# SCHEMATIC.net
KiCad netlist of a schematic drawn in EAGLE
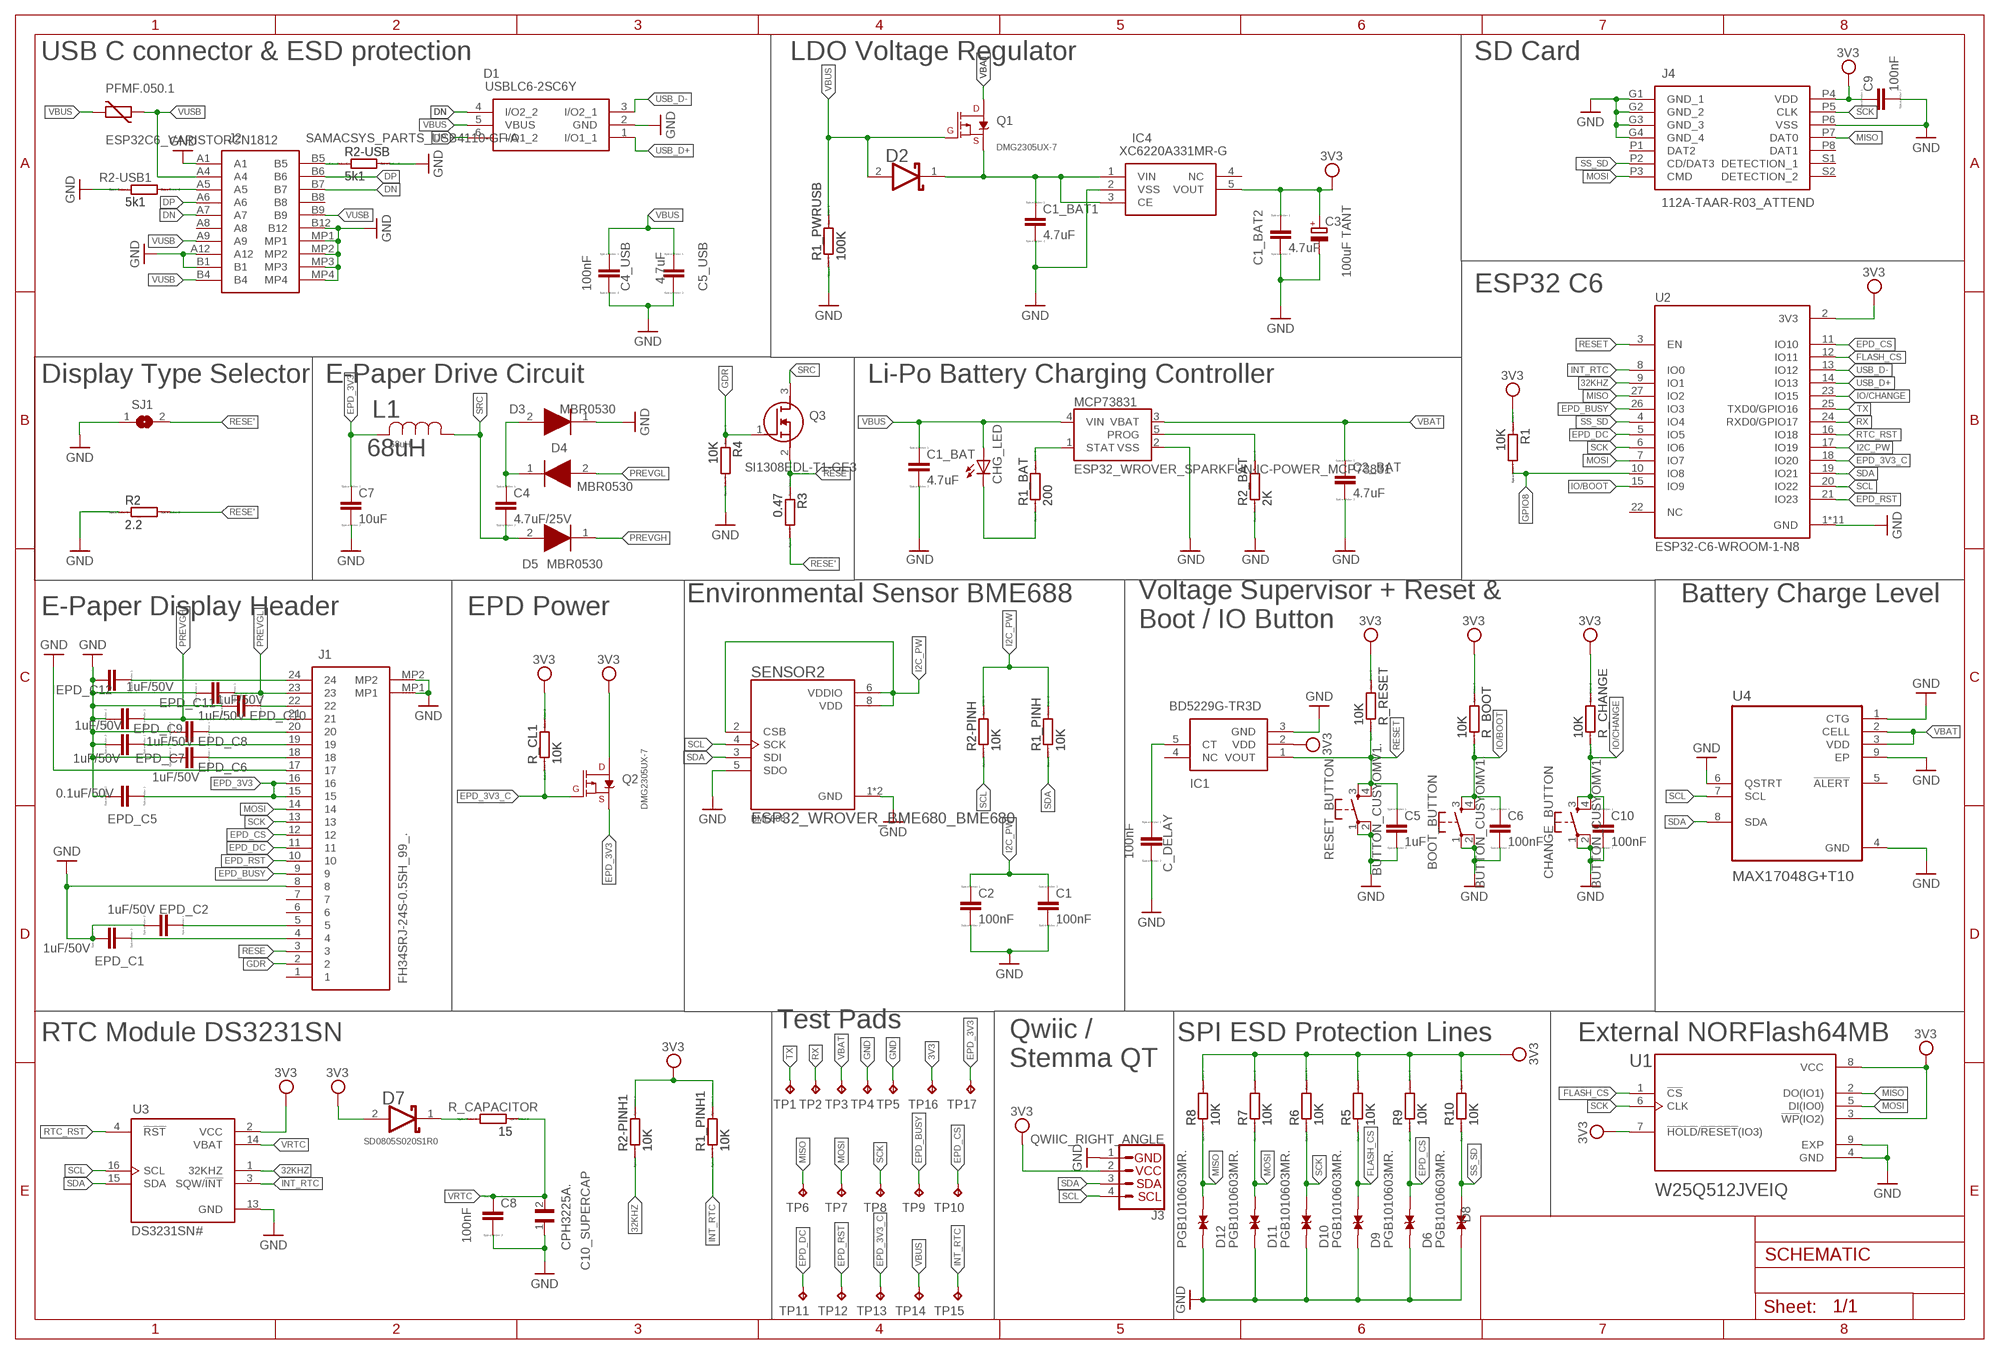
[diagram p0: schematic, sheet 1]

(export (version "E")
  (design (tool "Eeschema 10.0.6"))
  (components
    (comp (ref "BOOT_BUTTON")
      (value "BUTTON_CUSYOMV1.")
      (footprint "eagle-import:MYBUTTON")
      (libsource (lib "eagle-import") (part "BUTTON_CUSYOMV1."))
    )
    (comp (ref "C1")
      (value "100nF")
      (footprint "eagle-import:EAGLE-LTSPICE_C0402")
      (libsource (lib "eagle-import") (part "ESP32_WROVER_EAGLE-LTSPICE_CC0402"))
    )
    (comp (ref "C1_BAT")
      (value "4.7uF")
      (footprint "eagle-import:EAGLE-LTSPICE_C0402")
      (libsource (lib "eagle-import") (part "ESP32_WROVER_EAGLE-LTSPICE_CC0402"))
    )
    (comp (ref "C1_BAT1")
      (value "4.7uF")
      (footprint "eagle-import:EAGLE-LTSPICE_C0402")
      (libsource (lib "eagle-import") (part "ESP32_WROVER_EAGLE-LTSPICE_CC0402"))
    )
    (comp (ref "C1_BAT2")
      (value "4.7uF")
      (footprint "eagle-import:EAGLE-LTSPICE_C0402")
      (libsource (lib "eagle-import") (part "ESP32_WROVER_EAGLE-LTSPICE_CC0402"))
    )
    (comp (ref "C2")
      (value "100nF")
      (footprint "eagle-import:EAGLE-LTSPICE_C0402")
      (libsource (lib "eagle-import") (part "ESP32_WROVER_EAGLE-LTSPICE_CC0402"))
    )
    (comp (ref "C2_BAT")
      (value "4.7uF")
      (footprint "eagle-import:EAGLE-LTSPICE_C0402")
      (libsource (lib "eagle-import") (part "ESP32_WROVER_EAGLE-LTSPICE_CC0402"))
    )
    (comp (ref "C3")
      (value "100uF TANT")
      (footprint "eagle-import:RCL_CT3528")
      (libsource (lib "eagle-import") (part "RCL_CPOL-EUCT3528"))
    )
    (comp (ref "C4")
      (value "4.7uF/25V")
      (footprint "eagle-import:EAGLE-LTSPICE_C0402")
      (libsource (lib "eagle-import") (part "ESP32_WROVER_EAGLE-LTSPICE_CC0402"))
    )
    (comp (ref "C4_USB")
      (value "100nF")
      (footprint "eagle-import:EAGLE-LTSPICE_C0402")
      (libsource (lib "eagle-import") (part "ESP32_WROVER_EAGLE-LTSPICE_CC0402"))
    )
    (comp (ref "C5")
      (value "1uF")
      (footprint "eagle-import:EAGLE-LTSPICE_C0402")
      (libsource (lib "eagle-import") (part "ESP32_WROVER_EAGLE-LTSPICE_CC0402"))
    )
    (comp (ref "C5_USB")
      (value "4.7uF")
      (footprint "eagle-import:EAGLE-LTSPICE_C0402")
      (libsource (lib "eagle-import") (part "ESP32_WROVER_EAGLE-LTSPICE_CC0402"))
    )
    (comp (ref "C6")
      (value "100nF")
      (footprint "eagle-import:EAGLE-LTSPICE_C0402")
      (libsource (lib "eagle-import") (part "ESP32_WROVER_EAGLE-LTSPICE_CC0402"))
    )
    (comp (ref "C7")
      (value "10uF")
      (footprint "eagle-import:EAGLE-LTSPICE_C0402")
      (libsource (lib "eagle-import") (part "ESP32_WROVER_EAGLE-LTSPICE_CC0402"))
    )
    (comp (ref "C8")
      (value "100nF")
      (footprint "eagle-import:EAGLE-LTSPICE_C0402")
      (libsource (lib "eagle-import") (part "ESP32_WROVER_EAGLE-LTSPICE_CC0402"))
    )
    (comp (ref "C9")
      (value "100nF")
      (footprint "eagle-import:EAGLE-LTSPICE_C0402")
      (libsource (lib "eagle-import") (part "EAGLE-LTSPICE_CC0402"))
    )
    (comp (ref "C10")
      (value "100nF")
      (footprint "eagle-import:EAGLE-LTSPICE_C0402")
      (libsource (lib "eagle-import") (part "ESP32_WROVER_EAGLE-LTSPICE_CC0402"))
    )
    (comp (ref "C10_SUPERCAP")
      (value "CPH3225A.")
      (footprint "eagle-import:CAPCP3225X100N")
      (libsource (lib "eagle-import") (part "CPH3225A."))
    )
    (comp (ref "CHANGE_BUTTON")
      (value "BUTTON_CUSYOMV1.")
      (footprint "eagle-import:MYBUTTON")
      (libsource (lib "eagle-import") (part "BUTTON_CUSYOMV1."))
    )
    (comp (ref "CHG_LED")
      (value "ADAFRUIT_LEDCHIP-LED0603")
      (footprint "eagle-import:ADAFRUIT_CHIP-LED0603")
      (libsource (lib "eagle-import") (part "ADAFRUIT_LEDCHIP-LED0603"))
    )
    (comp (ref "C_DELAY")
      (value "100nF")
      (footprint "eagle-import:EAGLE-LTSPICE_C0402")
      (libsource (lib "eagle-import") (part "ESP32_WROVER_EAGLE-LTSPICE_CC0402"))
    )
    (comp (ref "D1")
      (value "USBLC6-2SC6Y")
      (footprint "eagle-import:SOT95P280X145-6N")
      (fields (field (name "MF") "STMicroelectronics"))
      (libsource (lib "eagle-import") (part "USBLC6-2SC6Y"))
    )
    (comp (ref "D2")
      (value "ESP32_WROVER_AVX---SD0805S020S1R0_AVX_SD0805S020S1R0_0_0AVX_SD0805S020S1R0_0_0")
      (footprint "eagle-import:ESP32_WROVER_AVX---SD0805S020S1R0_AVX_SD0805S020S1R0_0")
      (libsource (lib "eagle-import") (part "ESP32_WROVER_AVX---SD0805S020S1R0_AVX_SD0805S020S1R0_0_0AVX_SD0805S020S1R0_0_0"))
    )
    (comp (ref "D3")
      (value "MBR0530")
      (footprint "eagle-import:SOD3716X135N")
      (fields (field (name "MF") "ON Semiconductor"))
      (libsource (lib "eagle-import") (part "MBR0530"))
    )
    (comp (ref "D4")
      (value "MBR0530")
      (footprint "eagle-import:SOD3716X135N")
      (fields (field (name "MF") "ON Semiconductor"))
      (libsource (lib "eagle-import") (part "MBR0530"))
    )
    (comp (ref "D5")
      (value "MBR0530")
      (footprint "eagle-import:SOD3716X135N")
      (fields (field (name "MF") "ON Semiconductor"))
      (libsource (lib "eagle-import") (part "MBR0530"))
    )
    (comp (ref "D6")
      (value "PGB1010603MR.")
      (footprint "eagle-import:DIOC1608X36N")
      (libsource (lib "eagle-import") (part "PGB1010603MR."))
    )
    (comp (ref "D7")
      (value "ESP32_WROVER_AVX---SD0805S020S1R0_AVX_SD0805S020S1R0_0_0AVX_SD0805S020S1R0_0_0")
      (footprint "eagle-import:ESP32_WROVER_AVX---SD0805S020S1R0_AVX_SD0805S020S1R0_0")
      (fields (field (name "D7") "SD0805S020S1R0"))
      (libsource (lib "eagle-import") (part "ESP32_WROVER_AVX---SD0805S020S1R0_AVX_SD0805S020S1R0_0_0AVX_SD0805S020S1R0_0_0"))
    )
    (comp (ref "D8")
      (value "PGB1010603MR.")
      (footprint "eagle-import:DIOC1608X36N")
      (libsource (lib "eagle-import") (part "PGB1010603MR."))
    )
    (comp (ref "D9")
      (value "PGB1010603MR.")
      (footprint "eagle-import:DIOC1608X36N")
      (libsource (lib "eagle-import") (part "PGB1010603MR."))
    )
    (comp (ref "D10")
      (value "PGB1010603MR.")
      (footprint "eagle-import:DIOC1608X36N")
      (libsource (lib "eagle-import") (part "PGB1010603MR."))
    )
    (comp (ref "D11")
      (value "PGB1010603MR.")
      (footprint "eagle-import:DIOC1608X36N")
      (libsource (lib "eagle-import") (part "PGB1010603MR."))
    )
    (comp (ref "D12")
      (value "PGB1010603MR.")
      (footprint "eagle-import:DIOC1608X36N")
      (libsource (lib "eagle-import") (part "PGB1010603MR."))
    )
    (comp (ref "EPD_C1")
      (value "1uF/50V")
      (footprint "eagle-import:EAGLE-LTSPICE_C0402")
      (libsource (lib "eagle-import") (part "ESP32_WROVER_EAGLE-LTSPICE_CC0402"))
    )
    (comp (ref "EPD_C2")
      (value "1uF/50V")
      (footprint "eagle-import:EAGLE-LTSPICE_C0402")
      (libsource (lib "eagle-import") (part "ESP32_WROVER_EAGLE-LTSPICE_CC0402"))
    )
    (comp (ref "EPD_C5")
      (value "0.1uF/50V")
      (footprint "eagle-import:EAGLE-LTSPICE_C0402")
      (libsource (lib "eagle-import") (part "ESP32_WROVER_EAGLE-LTSPICE_CC0402"))
    )
    (comp (ref "EPD_C6")
      (value "1uF/50V")
      (footprint "eagle-import:EAGLE-LTSPICE_C0402")
      (libsource (lib "eagle-import") (part "ESP32_WROVER_EAGLE-LTSPICE_CC0402"))
    )
    (comp (ref "EPD_C7")
      (value "1uF/50V")
      (footprint "eagle-import:EAGLE-LTSPICE_C0402")
      (libsource (lib "eagle-import") (part "ESP32_WROVER_EAGLE-LTSPICE_CC0402"))
    )
    (comp (ref "EPD_C8")
      (value "1uF/50V")
      (footprint "eagle-import:EAGLE-LTSPICE_C0402")
      (libsource (lib "eagle-import") (part "ESP32_WROVER_EAGLE-LTSPICE_CC0402"))
    )
    (comp (ref "EPD_C9")
      (value "1uF/50V")
      (footprint "eagle-import:EAGLE-LTSPICE_C0402")
      (libsource (lib "eagle-import") (part "ESP32_WROVER_EAGLE-LTSPICE_CC0402"))
    )
    (comp (ref "EPD_C10")
      (value "1uF/50V")
      (footprint "eagle-import:EAGLE-LTSPICE_C0402")
      (libsource (lib "eagle-import") (part "ESP32_WROVER_EAGLE-LTSPICE_CC0402"))
    )
    (comp (ref "EPD_C11")
      (value "1uF/50V")
      (footprint "eagle-import:EAGLE-LTSPICE_C0402")
      (libsource (lib "eagle-import") (part "ESP32_WROVER_EAGLE-LTSPICE_CC0402"))
    )
    (comp (ref "EPD_C12")
      (value "1uF/50V")
      (footprint "eagle-import:EAGLE-LTSPICE_C0402")
      (libsource (lib "eagle-import") (part "ESP32_WROVER_EAGLE-LTSPICE_CC0402"))
    )
    (comp (ref "IC1")
      (value "BD5229G-TR3D")
      (footprint "eagle-import:SOT95P280X125-5N")
      (libsource (lib "eagle-import") (part "BD5229G-TR3D"))
    )
    (comp (ref "IC4")
      (value "XC6220A331MR-G")
      (footprint "eagle-import:SOT95P280X120-5N")
      (fields (field (name "MOUSER_PART_NUMBER") "865-XC6220A331MR-G"))
      (libsource (lib "eagle-import") (part "XC6220A331MR-G"))
    )
    (comp (ref "J1")
      (value "FH34SRJ-24S-0.5SH_99_.")
      (footprint "eagle-import:FH34SRJ24S05SH99")
      (libsource (lib "eagle-import") (part "FH34SRJ-24S-0.5SH_99_."))
    )
    (comp (ref "J2")
      (value "SAMACSYS_PARTS_USB4110-GF-A")
      (footprint "eagle-import:SAMACSYS_PARTS_USB4110GFA")
      (fields
        (field (name "MANUFACTURER_PART_NUMBER") "USB4110-GF-A")
        (field (name "MOUSER_PART_NUMBER") "640-USB4110-GF-A")
      )
      (libsource (lib "eagle-import") (part "SAMACSYS_PARTS_USB4110-GF-A"))
    )
    (comp (ref "J3")
      (value "QWIIC_RIGHT_ANGLE")
      (footprint "eagle-import:JST04_1MM_RA")
      (libsource (lib "eagle-import") (part "QWIIC_CONNECTORJS-1MM"))
    )
    (comp (ref "J4")
      (value "112A-TAAR-R03_ATTEND")
      (footprint "eagle-import:112ATAARR03ATTEND")
      (fields (field (name "MANUFACTURER_PART_NUMBER") "112A-TAAR-R03 ATTEND"))
      (libsource (lib "eagle-import") (part "112A-TAAR-R03_ATTEND"))
    )
    (comp (ref "L1")
      (value "68uH")
      (footprint "eagle-import:IND_4828-WE-TPC_WRE")
      (fields (field (name "IDK") "68uH"))
      (libsource (lib "eagle-import") (part "744043680IND_4828-WE-TPC_WRE"))
    )
    (comp (ref "MCP73831")
      (value "ESP32_WROVER_SPARKFUN-IC-POWER_MCP73831")
      (footprint "eagle-import:ESP32_WROVER_SPARKFUN-IC-POWER_SOT23-5")
      (libsource (lib "eagle-import") (part "ESP32_WROVER_SPARKFUN-IC-POWER_MCP73831"))
    )
    (comp (ref "PFMF.050.1")
      (value "ESP32C6_VARISTORCN1812")
      (footprint "eagle-import:ESP32C6_VARISTOR_CT_CN1812")
      (libsource (lib "eagle-import") (part "ESP32C6_VARISTORCN1812"))
    )
    (comp (ref "Q1")
      (value "20V/4.2A/52mΩ/1.4W")
      (footprint "eagle-import:ESP32_WROVER_SPARKFUN-DISCRETESEMI_SOT23-3")
      (fields (field (name "A") "DMG2305UX-7"))
      (libsource (lib "eagle-import") (part "ESP32_WROVER_SPARKFUN-DISCRETESEMI_MOSFET_PCH-DMG2305UX-7"))
    )
    (comp (ref "Q2")
      (value "20V/4.2A/52mΩ/1.4W")
      (footprint "eagle-import:ESP32_WROVER_SPARKFUN-DISCRETESEMI_SOT23-3")
      (fields (field (name "D") "DMG2305UX-7"))
      (libsource (lib "eagle-import") (part "ESP32_WROVER_SPARKFUN-DISCRETESEMI_MOSFET_PCH-DMG2305UX-7"))
    )
    (comp (ref "Q3")
      (value "SI1308EDL-T1-GE3")
      (footprint "eagle-import:SOT65P210X110-3N")
      (fields (field (name "MF") "Vishay Siliconix"))
      (libsource (lib "eagle-import") (part "SI1308EDL-T1-GE3"))
    )
    (comp (ref "R1")
      (value "10K")
      (footprint "eagle-import:ESP32_WROVER_EAGLE-LTSPICE_R0402")
      (libsource (lib "eagle-import") (part "ESP32_WROVER_EAGLE-LTSPICE_RR0402"))
    )
    (comp (ref "R1_BAT")
      (value "200")
      (footprint "eagle-import:ESP32_WROVER_EAGLE-LTSPICE_R0402")
      (libsource (lib "eagle-import") (part "ESP32_WROVER_EAGLE-LTSPICE_RR0402"))
    )
    (comp (ref "R1_PINH")
      (value "10K")
      (footprint "eagle-import:ESP32_WROVER_EAGLE-LTSPICE_R0402")
      (libsource (lib "eagle-import") (part "ESP32_WROVER_EAGLE-LTSPICE_RR0402"))
    )
    (comp (ref "R1_PINH1")
      (value "10K")
      (footprint "eagle-import:ESP32_WROVER_EAGLE-LTSPICE_R0402")
      (libsource (lib "eagle-import") (part "ESP32_WROVER_EAGLE-LTSPICE_RR0402"))
    )
    (comp (ref "R1_PWRUSB")
      (value "100K")
      (footprint "eagle-import:ESP32_WROVER_EAGLE-LTSPICE_R0402")
      (libsource (lib "eagle-import") (part "ESP32_WROVER_EAGLE-LTSPICE_RR0402"))
    )
    (comp (ref "R2")
      (value "2.2")
      (footprint "eagle-import:ESP32_WROVER_EAGLE-LTSPICE_R0402")
      (libsource (lib "eagle-import") (part "ESP32_WROVER_EAGLE-LTSPICE_RR0402"))
    )
    (comp (ref "R2-PINH")
      (value "10K")
      (footprint "eagle-import:ESP32_WROVER_EAGLE-LTSPICE_R0402")
      (libsource (lib "eagle-import") (part "ESP32_WROVER_EAGLE-LTSPICE_RR0402"))
    )
    (comp (ref "R2-PINH1")
      (value "10K")
      (footprint "eagle-import:ESP32_WROVER_EAGLE-LTSPICE_R0402")
      (libsource (lib "eagle-import") (part "ESP32_WROVER_EAGLE-LTSPICE_RR0402"))
    )
    (comp (ref "R2-USB")
      (value "5k1")
      (footprint "eagle-import:ESP32_WROVER_EAGLE-LTSPICE_R0402")
      (libsource (lib "eagle-import") (part "ESP32_WROVER_EAGLE-LTSPICE_RR0402"))
    )
    (comp (ref "R2-USB1")
      (value "5k1")
      (footprint "eagle-import:ESP32_WROVER_EAGLE-LTSPICE_R0402")
      (libsource (lib "eagle-import") (part "ESP32_WROVER_EAGLE-LTSPICE_RR0402"))
    )
    (comp (ref "R2_BAT")
      (value "2K")
      (footprint "eagle-import:ESP32_WROVER_EAGLE-LTSPICE_R0402")
      (libsource (lib "eagle-import") (part "ESP32_WROVER_EAGLE-LTSPICE_RR0402"))
    )
    (comp (ref "R3")
      (value "0.47")
      (footprint "eagle-import:ESP32_WROVER_EAGLE-LTSPICE_R0402")
      (libsource (lib "eagle-import") (part "ESP32_WROVER_EAGLE-LTSPICE_RR0402"))
    )
    (comp (ref "R4")
      (value "10K")
      (footprint "eagle-import:ESP32_WROVER_EAGLE-LTSPICE_R0402")
      (libsource (lib "eagle-import") (part "ESP32_WROVER_EAGLE-LTSPICE_RR0402"))
    )
    (comp (ref "R5")
      (value "10K")
      (footprint "eagle-import:ESP32_WROVER_EAGLE-LTSPICE_R0402")
      (libsource (lib "eagle-import") (part "ESP32_WROVER_EAGLE-LTSPICE_RR0402"))
    )
    (comp (ref "R6")
      (value "10K")
      (footprint "eagle-import:ESP32_WROVER_EAGLE-LTSPICE_R0402")
      (libsource (lib "eagle-import") (part "ESP32_WROVER_EAGLE-LTSPICE_RR0402"))
    )
    (comp (ref "R7")
      (value "10K")
      (footprint "eagle-import:ESP32_WROVER_EAGLE-LTSPICE_R0402")
      (libsource (lib "eagle-import") (part "ESP32_WROVER_EAGLE-LTSPICE_RR0402"))
    )
    (comp (ref "R8")
      (value "10K")
      (footprint "eagle-import:ESP32_WROVER_EAGLE-LTSPICE_R0402")
      (libsource (lib "eagle-import") (part "ESP32_WROVER_EAGLE-LTSPICE_RR0402"))
    )
    (comp (ref "R9")
      (value "10K")
      (footprint "eagle-import:ESP32_WROVER_EAGLE-LTSPICE_R0402")
      (libsource (lib "eagle-import") (part "ESP32_WROVER_EAGLE-LTSPICE_RR0402"))
    )
    (comp (ref "R10")
      (value "10K")
      (footprint "eagle-import:ESP32_WROVER_EAGLE-LTSPICE_R0402")
      (libsource (lib "eagle-import") (part "ESP32_WROVER_EAGLE-LTSPICE_RR0402"))
    )
    (comp (ref "RESET_BUTTON")
      (value "BUTTON_CUSYOMV1.")
      (footprint "eagle-import:MYBUTTON")
      (libsource (lib "eagle-import") (part "BUTTON_CUSYOMV1."))
    )
    (comp (ref "R_BOOT")
      (value "10K")
      (footprint "eagle-import:ESP32_WROVER_EAGLE-LTSPICE_R0402")
      (libsource (lib "eagle-import") (part "ESP32_WROVER_EAGLE-LTSPICE_RR0402"))
    )
    (comp (ref "R_CAPACITOR")
      (value "15")
      (footprint "eagle-import:ESP32_WROVER_EAGLE-LTSPICE_R0402")
      (libsource (lib "eagle-import") (part "ESP32_WROVER_EAGLE-LTSPICE_RR0402"))
    )
    (comp (ref "R_CHANGE")
      (value "10K")
      (footprint "eagle-import:ESP32_WROVER_EAGLE-LTSPICE_R0402")
      (libsource (lib "eagle-import") (part "ESP32_WROVER_EAGLE-LTSPICE_RR0402"))
    )
    (comp (ref "R_CL1")
      (value "10K")
      (footprint "eagle-import:ESP32_WROVER_EAGLE-LTSPICE_R0402")
      (libsource (lib "eagle-import") (part "ESP32_WROVER_EAGLE-LTSPICE_RR0402"))
    )
    (comp (ref "R_RESET")
      (value "10K")
      (footprint "eagle-import:ESP32_WROVER_EAGLE-LTSPICE_R0402")
      (libsource (lib "eagle-import") (part "ESP32_WROVER_EAGLE-LTSPICE_RR0402"))
    )
    (comp (ref "SENSOR2")
      (value "ESP32_WROVER_BME680_BME680")
      (footprint "eagle-import:ESP32_WROVER_BME680_PSON80P300X300X100-8N")
      (fields
        (field (name "MF") "Bosch Sensortec")
        (field (name "MP") "BME680")
        (field (name "ATR") "BME688")
        (field (name "B") "BME688")
      )
      (libsource (lib "eagle-import") (part "ESP32_WROVER_BME680_BME680"))
    )
    (comp (ref "SJ1")
      (value "SJ.")
      (footprint "eagle-import:SJ")
      (libsource (lib "eagle-import") (part "SJ."))
    )
    (comp (ref "TP1")
      (value "TPTP20R")
      (footprint "eagle-import:TP20R")
      (fields (field (name "3D_TP1") "RX"))
      (libsource (lib "eagle-import") (part "TPTP20R"))
    )
    (comp (ref "TP2")
      (value "TPTP20R")
      (footprint "eagle-import:TP20R")
      (libsource (lib "eagle-import") (part "TPTP20R"))
    )
    (comp (ref "TP3")
      (value "TPTP20R")
      (footprint "eagle-import:TP20R")
      (libsource (lib "eagle-import") (part "TPTP20R"))
    )
    (comp (ref "TP4")
      (value "TPTP20R")
      (footprint "eagle-import:TP20R")
      (libsource (lib "eagle-import") (part "TPTP20R"))
    )
    (comp (ref "TP5")
      (value "TPTP20R")
      (footprint "eagle-import:TP20R")
      (libsource (lib "eagle-import") (part "TPTP20R"))
    )
    (comp (ref "TP6")
      (value "TPTP20R")
      (footprint "eagle-import:TP20R")
      (libsource (lib "eagle-import") (part "TPTP20R"))
    )
    (comp (ref "TP7")
      (value "TPTP20R")
      (footprint "eagle-import:TP20R")
      (libsource (lib "eagle-import") (part "TPTP20R"))
    )
    (comp (ref "TP8")
      (value "TPTP20R")
      (footprint "eagle-import:TP20R")
      (libsource (lib "eagle-import") (part "TPTP20R"))
    )
    (comp (ref "TP9")
      (value "TPTP20R")
      (footprint "eagle-import:TP20R")
      (libsource (lib "eagle-import") (part "TPTP20R"))
    )
    (comp (ref "TP10")
      (value "TPTP20R")
      (footprint "eagle-import:TP20R")
      (libsource (lib "eagle-import") (part "TPTP20R"))
    )
    (comp (ref "TP11")
      (value "TPTP20R")
      (footprint "eagle-import:TP20R")
      (libsource (lib "eagle-import") (part "TPTP20R"))
    )
    (comp (ref "TP12")
      (value "TPTP20R")
      (footprint "eagle-import:TP20R")
      (libsource (lib "eagle-import") (part "TPTP20R"))
    )
    (comp (ref "TP13")
      (value "TPTP20R")
      (footprint "eagle-import:TP20R")
      (libsource (lib "eagle-import") (part "TPTP20R"))
    )
    (comp (ref "TP14")
      (value "TPTP20R")
      (footprint "eagle-import:TP20R")
      (libsource (lib "eagle-import") (part "TPTP20R"))
    )
    (comp (ref "TP15")
      (value "TPTP20R")
      (footprint "eagle-import:TP20R")
      (libsource (lib "eagle-import") (part "TPTP20R"))
    )
    (comp (ref "TP16")
      (value "TPTP20R")
      (footprint "eagle-import:TP20R")
      (libsource (lib "eagle-import") (part "TPTP20R"))
    )
    (comp (ref "TP17")
      (value "TPTP20R")
      (footprint "eagle-import:TP20R")
      (libsource (lib "eagle-import") (part "TPTP20R"))
    )
    (comp (ref "U1")
      (value "W25Q512JVEIQ")
      (footprint "eagle-import:SON127P600X800X80-9N")
      (fields (field (name "MF") "Winbond Electronics"))
      (libsource (lib "eagle-import") (part "W25Q512JVEIQ"))
    )
    (comp (ref "U2")
      (value "ESP32-C6-WROOM-1-N8")
      (footprint "eagle-import:XCVR_ESP32-C6-WROOM-1-N8")
      (fields (field (name "MF") "Espressif Systems"))
      (libsource (lib "eagle-import") (part "ESP32-C6-WROOM-1-N8"))
    )
    (comp (ref "U3")
      (value "DS3231SN#")
      (footprint "eagle-import:SOIC127P1032X265-16N")
      (fields (field (name "MF") "Analog Devices"))
      (libsource (lib "eagle-import") (part "DS3231SN#"))
    )
    (comp (ref "U4")
      (value "MAX17048G+T10")
      (footprint "eagle-import:SON50P200X200X80-9N")
      (fields (field (name "MF") "Analog Devices"))
      (libsource (lib "eagle-import") (part "MAX17048G+T10"))
    )
  )
  (nets
    (net (code "1") (name "3V3") (class "Default")
      (node (ref "C1_BAT2") (pin "1") (pinfunction "1_1") (pintype "passive"))
      (node (ref "C3") (pin "+") (pinfunction "+_+") (pintype "passive"))
      (node (ref "C9") (pin "1") (pinfunction "1_1") (pintype "passive"))
      (node (ref "D7") (pin "2") (pinfunction "ANODE_2") (pintype "bidirectional"))
      (node (ref "IC1") (pin "2") (pinfunction "VDD_2") (pintype "bidirectional"))
      (node (ref "IC4") (pin "5") (pinfunction "VOUT_5") (pintype "bidirectional"))
      (node (ref "J3") (pin "2") (pinfunction "2_2") (pintype "power_in"))
      (node (ref "J4") (pin "P4") (pinfunction "VDD_P4") (pintype "bidirectional"))
      (node (ref "Q2") (pin "3") (pinfunction "D_3") (pintype "bidirectional"))
      (node (ref "R1") (pin "1") (pinfunction "1_1") (pintype "passive"))
      (node (ref "R10") (pin "2") (pinfunction "2_2") (pintype "passive"))
      (node (ref "R1_PINH1") (pin "2") (pinfunction "2_2") (pintype "passive"))
      (node (ref "R2-PINH1") (pin "2") (pinfunction "2_2") (pintype "passive"))
      (node (ref "R5") (pin "2") (pinfunction "2_2") (pintype "passive"))
      (node (ref "R6") (pin "2") (pinfunction "2_2") (pintype "passive"))
      (node (ref "R7") (pin "2") (pinfunction "2_2") (pintype "passive"))
      (node (ref "R8") (pin "2") (pinfunction "2_2") (pintype "passive"))
      (node (ref "R9") (pin "2") (pinfunction "2_2") (pintype "passive"))
      (node (ref "R_BOOT") (pin "2") (pinfunction "2_2") (pintype "passive"))
      (node (ref "R_CHANGE") (pin "2") (pinfunction "2_2") (pintype "passive"))
      (node (ref "R_CL1") (pin "2") (pinfunction "2_2") (pintype "passive"))
      (node (ref "R_RESET") (pin "2") (pinfunction "2_2") (pintype "passive"))
      (node (ref "TP16") (pin "TP") (pinfunction "TP_TP") (pintype "input"))
      (node (ref "U1") (pin "3") (pinfunction "~{WP}(IO2)_3") (pintype "bidirectional"))
      (node (ref "U1") (pin "7") (pinfunction "~{HOLD}/~{RESET}(IO3)_7") (pintype "bidirectional"))
      (node (ref "U1") (pin "8") (pinfunction "VCC_8") (pintype "power_in"))
      (node (ref "U2") (pin "2") (pinfunction "3V3_2") (pintype "power_in"))
      (node (ref "U3") (pin "2") (pinfunction "VCC_2") (pintype "power_in"))
    )
    (net (code "2") (name "32KHZ") (class "Default")
      (node (ref "R2-PINH1") (pin "1") (pinfunction "1_1") (pintype "passive"))
      (node (ref "U2") (pin "9") (pinfunction "IO1_9") (pintype "bidirectional"))
      (node (ref "U3") (pin "1") (pinfunction "32KHZ_1") (pintype "output"))
    )
    (net (code "3") (name "DN") (class "Default")
      (node (ref "D1") (pin "4") (pinfunction "I/O2_2_4") (pintype "bidirectional"))
      (node (ref "J2") (pin "A7") (pinfunction "A7_A7") (pintype "bidirectional"))
      (node (ref "J2") (pin "B7") (pinfunction "B7_B7") (pintype "bidirectional"))
    )
    (net (code "4") (name "DP") (class "Default")
      (node (ref "D1") (pin "6") (pinfunction "I/O1_2_6") (pintype "bidirectional"))
      (node (ref "J2") (pin "A6") (pinfunction "A6_A6") (pintype "bidirectional"))
      (node (ref "J2") (pin "B6") (pinfunction "B6_B6") (pintype "bidirectional"))
    )
    (net (code "5") (name "EPD_3V3") (class "Default")
      (node (ref "C7") (pin "1") (pinfunction "1_1") (pintype "passive"))
      (node (ref "EPD_C5") (pin "1") (pinfunction "1_1") (pintype "passive"))
      (node (ref "J1") (pin "15") (pinfunction "15_15") (pintype "bidirectional"))
      (node (ref "J1") (pin "16") (pinfunction "16_16") (pintype "bidirectional"))
      (node (ref "L1") (pin "2") (pinfunction "2_2") (pintype "passive"))
      (node (ref "Q2") (pin "2") (pinfunction "S_2") (pintype "bidirectional"))
      (node (ref "TP17") (pin "TP") (pinfunction "TP_TP") (pintype "input"))
    )
    (net (code "6") (name "EPD_3V3_C") (class "Default")
      (node (ref "Q2") (pin "1") (pinfunction "G_1") (pintype "bidirectional"))
      (node (ref "R_CL1") (pin "1") (pinfunction "1_1") (pintype "passive"))
      (node (ref "TP13") (pin "TP") (pinfunction "TP_TP") (pintype "input"))
      (node (ref "U2") (pin "18") (pinfunction "IO20_18") (pintype "bidirectional"))
    )
    (net (code "7") (name "EPD_BUSY") (class "Default")
      (node (ref "J1") (pin "9") (pinfunction "9_9") (pintype "bidirectional"))
      (node (ref "TP9") (pin "TP") (pinfunction "TP_TP") (pintype "input"))
      (node (ref "U2") (pin "26") (pinfunction "IO3_26") (pintype "bidirectional"))
    )
    (net (code "8") (name "EPD_CS") (class "Default")
      (node (ref "D6") (pin "2") (pinfunction "2_2") (pintype "passive"))
      (node (ref "J1") (pin "12") (pinfunction "12_12") (pintype "bidirectional"))
      (node (ref "R9") (pin "1") (pinfunction "1_1") (pintype "passive"))
      (node (ref "TP10") (pin "TP") (pinfunction "TP_TP") (pintype "input"))
      (node (ref "U2") (pin "11") (pinfunction "IO10_11") (pintype "bidirectional"))
    )
    (net (code "9") (name "EPD_DC") (class "Default")
      (node (ref "J1") (pin "11") (pinfunction "11_11") (pintype "bidirectional"))
      (node (ref "TP11") (pin "TP") (pinfunction "TP_TP") (pintype "input"))
      (node (ref "U2") (pin "5") (pinfunction "IO5_5") (pintype "bidirectional"))
    )
    (net (code "10") (name "EPD_RST") (class "Default")
      (node (ref "J1") (pin "10") (pinfunction "10_10") (pintype "bidirectional"))
      (node (ref "TP12") (pin "TP") (pinfunction "TP_TP") (pintype "input"))
      (node (ref "U2") (pin "21") (pinfunction "IO23_21") (pintype "bidirectional"))
    )
    (net (code "11") (name "FLASH_CS") (class "Default")
      (node (ref "D9") (pin "2") (pinfunction "2_2") (pintype "passive"))
      (node (ref "R5") (pin "1") (pinfunction "1_1") (pintype "passive"))
      (node (ref "U1") (pin "1") (pinfunction "~{CS}_1") (pintype "input"))
      (node (ref "U2") (pin "12") (pinfunction "IO11_12") (pintype "bidirectional"))
    )
    (net (code "12") (name "GDR") (class "Default")
      (node (ref "J1") (pin "2") (pinfunction "2_2") (pintype "bidirectional"))
      (node (ref "Q3") (pin "1") (pinfunction "G_1") (pintype "bidirectional"))
      (node (ref "R4") (pin "1") (pinfunction "1_1") (pintype "passive"))
    )
    (net (code "13") (name "GND") (class "Default")
      (node (ref "BOOT_BUTTON") (pin "1") (pinfunction "1_1") (pintype "passive"))
      (node (ref "BOOT_BUTTON") (pin "2") (pinfunction "2_2") (pintype "passive"))
      (node (ref "C1") (pin "2") (pinfunction "2_2") (pintype "passive"))
      (node (ref "C10") (pin "2") (pinfunction "2_2") (pintype "passive"))
      (node (ref "C10_SUPERCAP") (pin "1") (pinfunction "1_1") (pintype "passive"))
      (node (ref "C1_BAT") (pin "2") (pinfunction "2_2") (pintype "passive"))
      (node (ref "C1_BAT1") (pin "2") (pinfunction "2_2") (pintype "passive"))
      (node (ref "C1_BAT2") (pin "2") (pinfunction "2_2") (pintype "passive"))
      (node (ref "C2") (pin "2") (pinfunction "2_2") (pintype "passive"))
      (node (ref "C2_BAT") (pin "2") (pinfunction "2_2") (pintype "passive"))
      (node (ref "C3") (pin "-") (pinfunction "-_-") (pintype "passive"))
      (node (ref "C4_USB") (pin "2") (pinfunction "2_2") (pintype "passive"))
      (node (ref "C5") (pin "2") (pinfunction "2_2") (pintype "passive"))
      (node (ref "C5_USB") (pin "2") (pinfunction "2_2") (pintype "passive"))
      (node (ref "C6") (pin "2") (pinfunction "2_2") (pintype "passive"))
      (node (ref "C7") (pin "2") (pinfunction "2_2") (pintype "passive"))
      (node (ref "C8") (pin "2") (pinfunction "2_2") (pintype "passive"))
      (node (ref "C9") (pin "2") (pinfunction "2_2") (pintype "passive"))
      (node (ref "CHANGE_BUTTON") (pin "1") (pinfunction "1_1") (pintype "passive"))
      (node (ref "CHANGE_BUTTON") (pin "2") (pinfunction "2_2") (pintype "passive"))
      (node (ref "C_DELAY") (pin "2") (pinfunction "2_2") (pintype "passive"))
      (node (ref "D1") (pin "2") (pinfunction "GND_2") (pintype "bidirectional"))
      (node (ref "D10") (pin "1") (pinfunction "1_1") (pintype "passive"))
      (node (ref "D11") (pin "1") (pinfunction "1_1") (pintype "passive"))
      (node (ref "D12") (pin "1") (pinfunction "1_1") (pintype "passive"))
      (node (ref "D3") (pin "1") (pinfunction "K_1") (pintype "bidirectional"))
      (node (ref "D6") (pin "1") (pinfunction "1_1") (pintype "passive"))
      (node (ref "D8") (pin "1") (pinfunction "1_1") (pintype "passive"))
      (node (ref "D9") (pin "1") (pinfunction "1_1") (pintype "passive"))
      (node (ref "EPD_C1") (pin "2") (pinfunction "2_2") (pintype "passive"))
      (node (ref "EPD_C10") (pin "2") (pinfunction "2_2") (pintype "passive"))
      (node (ref "EPD_C11") (pin "2") (pinfunction "2_2") (pintype "passive"))
      (node (ref "EPD_C12") (pin "2") (pinfunction "2_2") (pintype "passive"))
      (node (ref "EPD_C2") (pin "2") (pinfunction "2_2") (pintype "passive"))
      (node (ref "EPD_C5") (pin "2") (pinfunction "2_2") (pintype "passive"))
      (node (ref "EPD_C6") (pin "2") (pinfunction "2_2") (pintype "passive"))
      (node (ref "EPD_C7") (pin "2") (pinfunction "2_2") (pintype "passive"))
      (node (ref "EPD_C8") (pin "2") (pinfunction "2_2") (pintype "passive"))
      (node (ref "EPD_C9") (pin "2") (pinfunction "2_2") (pintype "passive"))
      (node (ref "IC1") (pin "3") (pinfunction "GND_3") (pintype "bidirectional"))
      (node (ref "IC4") (pin "2") (pinfunction "VSS_2") (pintype "bidirectional"))
      (node (ref "J1") (pin "17") (pinfunction "17_17") (pintype "bidirectional"))
      (node (ref "J1") (pin "8") (pinfunction "8_8") (pintype "bidirectional"))
      (node (ref "J1") (pin "MP1") (pinfunction "MP1_MP1") (pintype "bidirectional"))
      (node (ref "J1") (pin "MP2") (pinfunction "MP2_MP2") (pintype "bidirectional"))
      (node (ref "J2") (pin "A1") (pinfunction "A1_A1") (pintype "bidirectional"))
      (node (ref "J2") (pin "A12") (pinfunction "A12_A12") (pintype "bidirectional"))
      (node (ref "J2") (pin "B1") (pinfunction "B1_B1") (pintype "bidirectional"))
      (node (ref "J2") (pin "B12") (pinfunction "B12_B12") (pintype "bidirectional"))
      (node (ref "J2") (pin "MP1") (pinfunction "MP1_MP1") (pintype "bidirectional"))
      (node (ref "J2") (pin "MP2") (pinfunction "MP2_MP2") (pintype "bidirectional"))
      (node (ref "J2") (pin "MP3") (pinfunction "MP3_MP3") (pintype "bidirectional"))
      (node (ref "J2") (pin "MP4") (pinfunction "MP4_MP4") (pintype "bidirectional"))
      (node (ref "J3") (pin "1") (pinfunction "1_1") (pintype "power_in"))
      (node (ref "J4") (pin "G1") (pinfunction "GND_1_G1") (pintype "bidirectional"))
      (node (ref "J4") (pin "G2") (pinfunction "GND_2_G2") (pintype "bidirectional"))
      (node (ref "J4") (pin "G3") (pinfunction "GND_3_G3") (pintype "bidirectional"))
      (node (ref "J4") (pin "G4") (pinfunction "GND_4_G4") (pintype "bidirectional"))
      (node (ref "J4") (pin "P6") (pinfunction "VSS_P6") (pintype "bidirectional"))
      (node (ref "MCP73831") (pin "2") (pinfunction "VSS_2") (pintype "power_in"))
      (node (ref "R1_PWRUSB") (pin "1") (pinfunction "1_1") (pintype "passive"))
      (node (ref "R2") (pin "1") (pinfunction "1_1") (pintype "passive"))
      (node (ref "R2-USB") (pin "2") (pinfunction "2_2") (pintype "passive"))
      (node (ref "R2-USB1") (pin "1") (pinfunction "1_1") (pintype "passive"))
      (node (ref "R2_BAT") (pin "1") (pinfunction "1_1") (pintype "passive"))
      (node (ref "R4") (pin "2") (pinfunction "2_2") (pintype "passive"))
      (node (ref "RESET_BUTTON") (pin "1") (pinfunction "1_1") (pintype "passive"))
      (node (ref "RESET_BUTTON") (pin "2") (pinfunction "2_2") (pintype "passive"))
      (node (ref "SENSOR2") (pin "1") (pinfunction "GND_1") (pintype "power_in"))
      (node (ref "SENSOR2") (pin "5") (pinfunction "SDO_5") (pintype "bidirectional"))
      (node (ref "SENSOR2") (pin "7") (pinfunction "GND_7") (pintype "power_in"))
      (node (ref "SJ1") (pin "1") (pinfunction "1_1") (pintype "passive"))
      (node (ref "TP4") (pin "TP") (pinfunction "TP_TP") (pintype "input"))
      (node (ref "TP5") (pin "TP") (pinfunction "TP_TP") (pintype "input"))
      (node (ref "U1") (pin "4") (pinfunction "GND_4") (pintype "power_in"))
      (node (ref "U1") (pin "9") (pinfunction "EXP_9") (pintype "passive"))
      (node (ref "U2") (pin "1") (pinfunction "GND_1") (pintype "power_in"))
      (node (ref "U2") (pin "28") (pinfunction "GND_28") (pintype "power_in"))
      (node (ref "U2") (pin "29_1") (pinfunction "GND_29_1") (pintype "power_in"))
      (node (ref "U2") (pin "29_2") (pinfunction "GND_29_2") (pintype "power_in"))
      (node (ref "U2") (pin "29_3") (pinfunction "GND_29_3") (pintype "power_in"))
      (node (ref "U2") (pin "29_4") (pinfunction "GND_29_4") (pintype "power_in"))
      (node (ref "U2") (pin "29_5") (pinfunction "GND_29_5") (pintype "power_in"))
      (node (ref "U2") (pin "29_6") (pinfunction "GND_29_6") (pintype "power_in"))
      (node (ref "U2") (pin "29_7") (pinfunction "GND_29_7") (pintype "power_in"))
      (node (ref "U2") (pin "29_8") (pinfunction "GND_29_8") (pintype "power_in"))
      (node (ref "U2") (pin "29_9") (pinfunction "GND_29_9") (pintype "power_in"))
      (node (ref "U3") (pin "13") (pinfunction "GND_13") (pintype "power_in"))
      (node (ref "U4") (pin "1") (pinfunction "CTG_1") (pintype "power_in"))
      (node (ref "U4") (pin "4") (pinfunction "GND_4") (pintype "power_in"))
      (node (ref "U4") (pin "6") (pinfunction "QSTRT_6") (pintype "input"))
      (node (ref "U4") (pin "9") (pinfunction "EP_9") (pintype "power_in"))
    )
    (net (code "14") (name "GPIO8") (class "Default")
      (node (ref "R1") (pin "2") (pinfunction "2_2") (pintype "passive"))
      (node (ref "U2") (pin "10") (pinfunction "IO8_10") (pintype "bidirectional"))
    )
    (net (code "15") (name "I2C_PW") (class "Default")
      (node (ref "C1") (pin "1") (pinfunction "1_1") (pintype "passive"))
      (node (ref "C2") (pin "1") (pinfunction "1_1") (pintype "passive"))
      (node (ref "R1_PINH") (pin "2") (pinfunction "2_2") (pintype "passive"))
      (node (ref "R2-PINH") (pin "2") (pinfunction "2_2") (pintype "passive"))
      (node (ref "SENSOR2") (pin "2") (pinfunction "CSB_2") (pintype "input"))
      (node (ref "SENSOR2") (pin "6") (pinfunction "VDDIO_6") (pintype "power_in"))
      (node (ref "SENSOR2") (pin "8") (pinfunction "VDD_8") (pintype "power_in"))
      (node (ref "U2") (pin "17") (pinfunction "IO19_17") (pintype "bidirectional"))
    )
    (net (code "16") (name "INT_RTC") (class "Default")
      (node (ref "R1_PINH1") (pin "1") (pinfunction "1_1") (pintype "passive"))
      (node (ref "TP15") (pin "TP") (pinfunction "TP_TP") (pintype "input"))
      (node (ref "U2") (pin "8") (pinfunction "IO0_8") (pintype "bidirectional"))
      (node (ref "U3") (pin "3") (pinfunction "SQW/~{INT}_3") (pintype "output"))
    )
    (net (code "17") (name "IO{slash}BOOT") (class "Default")
      (node (ref "BOOT_BUTTON") (pin "3") (pinfunction "3_3") (pintype "passive"))
      (node (ref "BOOT_BUTTON") (pin "4") (pinfunction "4_4") (pintype "passive"))
      (node (ref "C6") (pin "1") (pinfunction "1_1") (pintype "passive"))
      (node (ref "R_BOOT") (pin "1") (pinfunction "1_1") (pintype "passive"))
      (node (ref "U2") (pin "15") (pinfunction "IO9_15") (pintype "bidirectional"))
    )
    (net (code "18") (name "IO{slash}CHANGE") (class "Default")
      (node (ref "C10") (pin "1") (pinfunction "1_1") (pintype "passive"))
      (node (ref "CHANGE_BUTTON") (pin "3") (pinfunction "3_3") (pintype "passive"))
      (node (ref "CHANGE_BUTTON") (pin "4") (pinfunction "4_4") (pintype "passive"))
      (node (ref "R_CHANGE") (pin "1") (pinfunction "1_1") (pintype "passive"))
      (node (ref "U2") (pin "23") (pinfunction "IO15_23") (pintype "bidirectional"))
    )
    (net (code "19") (name "MISO") (class "Default")
      (node (ref "D12") (pin "2") (pinfunction "2_2") (pintype "passive"))
      (node (ref "J4") (pin "P7") (pinfunction "DAT0_P7") (pintype "bidirectional"))
      (node (ref "R8") (pin "1") (pinfunction "1_1") (pintype "passive"))
      (node (ref "TP6") (pin "TP") (pinfunction "TP_TP") (pintype "input"))
      (node (ref "U1") (pin "2") (pinfunction "DO(IO1)_2") (pintype "bidirectional"))
      (node (ref "U2") (pin "27") (pinfunction "IO2_27") (pintype "bidirectional"))
    )
    (net (code "20") (name "MOSI") (class "Default")
      (node (ref "D11") (pin "2") (pinfunction "2_2") (pintype "passive"))
      (node (ref "J1") (pin "14") (pinfunction "14_14") (pintype "bidirectional"))
      (node (ref "J4") (pin "P3") (pinfunction "CMD_P3") (pintype "bidirectional"))
      (node (ref "R7") (pin "1") (pinfunction "1_1") (pintype "passive"))
      (node (ref "TP7") (pin "TP") (pinfunction "TP_TP") (pintype "input"))
      (node (ref "U1") (pin "5") (pinfunction "DI(IO0)_5") (pintype "bidirectional"))
      (node (ref "U2") (pin "7") (pinfunction "IO7_7") (pintype "bidirectional"))
    )
    (net (code "21") (name "Net-(CHG_LED-PadC)") (class "Default")
      (node (ref "CHG_LED") (pin "C") (pinfunction "C_C") (pintype "passive"))
      (node (ref "R1_BAT") (pin "1") (pinfunction "1_1") (pintype "passive"))
    )
    (net (code "22") (name "Net-(D2-CATHODE)") (class "Default")
      (node (ref "C1_BAT1") (pin "1") (pinfunction "1_1") (pintype "passive"))
      (node (ref "D2") (pin "1") (pinfunction "CATHODE_1") (pintype "bidirectional"))
      (node (ref "IC4") (pin "1") (pinfunction "VIN_1") (pintype "bidirectional"))
      (node (ref "IC4") (pin "3") (pinfunction "CE_3") (pintype "bidirectional"))
      (node (ref "Q1") (pin "2") (pinfunction "S_2") (pintype "bidirectional"))
    )
    (net (code "23") (name "Net-(D3-A)") (class "Default")
      (node (ref "C4") (pin "1") (pinfunction "1_1") (pintype "passive"))
      (node (ref "D3") (pin "2") (pinfunction "A_2") (pintype "bidirectional"))
      (node (ref "D4") (pin "1") (pinfunction "K_1") (pintype "bidirectional"))
    )
    (net (code "24") (name "Net-(D7-CATHODE)") (class "Default")
      (node (ref "D7") (pin "1") (pinfunction "CATHODE_1") (pintype "bidirectional"))
      (node (ref "R_CAPACITOR") (pin "2") (pinfunction "2_2") (pintype "passive"))
    )
    (net (code "25") (name "Net-(EPD_C1-Pad1)") (class "Default")
      (node (ref "EPD_C1") (pin "1") (pinfunction "1_1") (pintype "passive"))
      (node (ref "J1") (pin "4") (pinfunction "4_4") (pintype "bidirectional"))
    )
    (net (code "26") (name "Net-(EPD_C2-Pad1)") (class "Default")
      (node (ref "EPD_C2") (pin "1") (pinfunction "1_1") (pintype "passive"))
      (node (ref "J1") (pin "5") (pinfunction "5_5") (pintype "bidirectional"))
    )
    (net (code "27") (name "Net-(EPD_C6-Pad1)") (class "Default")
      (node (ref "EPD_C6") (pin "1") (pinfunction "1_1") (pintype "passive"))
      (node (ref "J1") (pin "18") (pinfunction "18_18") (pintype "bidirectional"))
    )
    (net (code "28") (name "Net-(EPD_C7-Pad1)") (class "Default")
      (node (ref "EPD_C7") (pin "1") (pinfunction "1_1") (pintype "passive"))
      (node (ref "J1") (pin "19") (pinfunction "19_19") (pintype "bidirectional"))
    )
    (net (code "29") (name "Net-(EPD_C8-Pad1)") (class "Default")
      (node (ref "EPD_C8") (pin "1") (pinfunction "1_1") (pintype "passive"))
      (node (ref "J1") (pin "20") (pinfunction "20_20") (pintype "bidirectional"))
    )
    (net (code "30") (name "Net-(EPD_C10-Pad1)") (class "Default")
      (node (ref "EPD_C10") (pin "1") (pinfunction "1_1") (pintype "passive"))
      (node (ref "J1") (pin "22") (pinfunction "22_22") (pintype "bidirectional"))
    )
    (net (code "31") (name "Net-(EPD_C12-Pad1)") (class "Default")
      (node (ref "EPD_C12") (pin "1") (pinfunction "1_1") (pintype "passive"))
      (node (ref "J1") (pin "24") (pinfunction "24_24") (pintype "bidirectional"))
    )
    (net (code "32") (name "Net-(IC1-CT)") (class "Default")
      (node (ref "C_DELAY") (pin "1") (pinfunction "1_1") (pintype "passive"))
      (node (ref "IC1") (pin "5") (pinfunction "CT_5") (pintype "bidirectional"))
    )
    (net (code "33") (name "Net-(J2-PadA5)") (class "Default")
      (node (ref "J2") (pin "A5") (pinfunction "A5_A5") (pintype "bidirectional"))
      (node (ref "R2-USB1") (pin "2") (pinfunction "2_2") (pintype "passive"))
    )
    (net (code "34") (name "Net-(J2-PadB5)") (class "Default")
      (node (ref "J2") (pin "B5") (pinfunction "B5_B5") (pintype "bidirectional"))
      (node (ref "R2-USB") (pin "1") (pinfunction "1_1") (pintype "passive"))
    )
    (net (code "35") (name "Net-(MCP73831-PROG)") (class "Default")
      (node (ref "MCP73831") (pin "5") (pinfunction "PROG_5") (pintype "input"))
      (node (ref "R2_BAT") (pin "2") (pinfunction "2_2") (pintype "passive"))
    )
    (net (code "36") (name "Net-(MCP73831-STAT)") (class "Default")
      (node (ref "MCP73831") (pin "1") (pinfunction "STAT_1") (pintype "output"))
      (node (ref "R1_BAT") (pin "2") (pinfunction "2_2") (pintype "passive"))
    )
    (net (code "37") (name "PREVGH") (class "Default")
      (node (ref "D5") (pin "1") (pinfunction "K_1") (pintype "bidirectional"))
      (node (ref "EPD_C9") (pin "1") (pinfunction "1_1") (pintype "passive"))
      (node (ref "J1") (pin "21") (pinfunction "21_21") (pintype "bidirectional"))
    )
    (net (code "38") (name "PREVGL") (class "Default")
      (node (ref "D4") (pin "2") (pinfunction "A_2") (pintype "bidirectional"))
      (node (ref "EPD_C11") (pin "1") (pinfunction "1_1") (pintype "passive"))
      (node (ref "J1") (pin "23") (pinfunction "23_23") (pintype "bidirectional"))
    )
    (net (code "39") (name "RESE") (class "Default")
      (node (ref "J1") (pin "3") (pinfunction "3_3") (pintype "bidirectional"))
      (node (ref "Q3") (pin "2") (pinfunction "S_2") (pintype "bidirectional"))
      (node (ref "R3") (pin "1") (pinfunction "1_1") (pintype "passive"))
    )
    (net (code "40") (name "RESE'") (class "Default")
      (node (ref "R2") (pin "2") (pinfunction "2_2") (pintype "passive"))
      (node (ref "R3") (pin "2") (pinfunction "2_2") (pintype "passive"))
      (node (ref "SJ1") (pin "2") (pinfunction "2_2") (pintype "passive"))
    )
    (net (code "41") (name "RESET") (class "Default")
      (node (ref "C5") (pin "1") (pinfunction "1_1") (pintype "passive"))
      (node (ref "IC1") (pin "1") (pinfunction "VOUT_1") (pintype "bidirectional"))
      (node (ref "RESET_BUTTON") (pin "3") (pinfunction "3_3") (pintype "passive"))
      (node (ref "RESET_BUTTON") (pin "4") (pinfunction "4_4") (pintype "passive"))
      (node (ref "R_RESET") (pin "1") (pinfunction "1_1") (pintype "passive"))
      (node (ref "U2") (pin "3") (pinfunction "EN_3") (pintype "input"))
    )
    (net (code "42") (name "RTC_RST") (class "Default")
      (node (ref "U2") (pin "16") (pinfunction "IO18_16") (pintype "bidirectional"))
      (node (ref "U3") (pin "4") (pinfunction "~{RST}_4") (pintype "input"))
    )
    (net (code "43") (name "RX") (class "Default")
      (node (ref "TP2") (pin "TP") (pinfunction "TP_TP") (pintype "input"))
      (node (ref "U2") (pin "24") (pinfunction "RXD0/GPIO17_24") (pintype "bidirectional"))
    )
    (net (code "44") (name "SCK") (class "Default")
      (node (ref "D10") (pin "2") (pinfunction "2_2") (pintype "passive"))
      (node (ref "J1") (pin "13") (pinfunction "13_13") (pintype "bidirectional"))
      (node (ref "J4") (pin "P5") (pinfunction "CLK_P5") (pintype "bidirectional"))
      (node (ref "R6") (pin "1") (pinfunction "1_1") (pintype "passive"))
      (node (ref "TP8") (pin "TP") (pinfunction "TP_TP") (pintype "input"))
      (node (ref "U1") (pin "6") (pinfunction "CLK_6") (pintype "input"))
      (node (ref "U2") (pin "6") (pinfunction "IO6_6") (pintype "bidirectional"))
    )
    (net (code "45") (name "SCL") (class "Default")
      (node (ref "J3") (pin "4") (pinfunction "4_4") (pintype "passive"))
      (node (ref "R2-PINH") (pin "1") (pinfunction "1_1") (pintype "passive"))
      (node (ref "SENSOR2") (pin "4") (pinfunction "SCK_4") (pintype "input"))
      (node (ref "U2") (pin "20") (pinfunction "IO22_20") (pintype "bidirectional"))
      (node (ref "U3") (pin "16") (pinfunction "SCL_16") (pintype "input"))
      (node (ref "U4") (pin "7") (pinfunction "SCL_7") (pintype "input"))
    )
    (net (code "46") (name "SDA") (class "Default")
      (node (ref "J3") (pin "3") (pinfunction "3_3") (pintype "passive"))
      (node (ref "R1_PINH") (pin "1") (pinfunction "1_1") (pintype "passive"))
      (node (ref "SENSOR2") (pin "3") (pinfunction "SDI_3") (pintype "bidirectional"))
      (node (ref "U2") (pin "19") (pinfunction "IO21_19") (pintype "bidirectional"))
      (node (ref "U3") (pin "15") (pinfunction "SDA_15") (pintype "bidirectional"))
      (node (ref "U4") (pin "8") (pinfunction "SDA_8") (pintype "bidirectional"))
    )
    (net (code "47") (name "SRC") (class "Default")
      (node (ref "C4") (pin "2") (pinfunction "2_2") (pintype "passive"))
      (node (ref "D5") (pin "2") (pinfunction "A_2") (pintype "bidirectional"))
      (node (ref "L1") (pin "1") (pinfunction "1_1") (pintype "passive"))
      (node (ref "Q3") (pin "3") (pinfunction "D_3") (pintype "bidirectional"))
    )
    (net (code "48") (name "SS_SD") (class "Default")
      (node (ref "D8") (pin "2") (pinfunction "2_2") (pintype "passive"))
      (node (ref "J4") (pin "P2") (pinfunction "CD/DAT3_P2") (pintype "bidirectional"))
      (node (ref "R10") (pin "1") (pinfunction "1_1") (pintype "passive"))
      (node (ref "U2") (pin "4") (pinfunction "IO4_4") (pintype "bidirectional"))
    )
    (net (code "49") (name "TX") (class "Default")
      (node (ref "TP1") (pin "TP") (pinfunction "TP_TP") (pintype "input"))
      (node (ref "U2") (pin "25") (pinfunction "TXD0/GPIO16_25") (pintype "bidirectional"))
    )
    (net (code "50") (name "USB_D+") (class "Default")
      (node (ref "D1") (pin "1") (pinfunction "I/O1_1_1") (pintype "bidirectional"))
      (node (ref "U2") (pin "14") (pinfunction "IO13_14") (pintype "bidirectional"))
    )
    (net (code "51") (name "USB_D-") (class "Default")
      (node (ref "D1") (pin "3") (pinfunction "I/O2_1_3") (pintype "bidirectional"))
      (node (ref "U2") (pin "13") (pinfunction "IO12_13") (pintype "bidirectional"))
    )
    (net (code "52") (name "VBAT") (class "Default")
      (node (ref "C2_BAT") (pin "1") (pinfunction "1_1") (pintype "passive"))
      (node (ref "MCP73831") (pin "3") (pinfunction "VBAT_3") (pintype "power_in"))
      (node (ref "Q1") (pin "3") (pinfunction "D_3") (pintype "bidirectional"))
      (node (ref "TP3") (pin "TP") (pinfunction "TP_TP") (pintype "input"))
      (node (ref "U4") (pin "2") (pinfunction "CELL_2") (pintype "power_in"))
      (node (ref "U4") (pin "3") (pinfunction "VDD_3") (pintype "power_in"))
    )
    (net (code "53") (name "VBUS") (class "Default")
      (node (ref "C1_BAT") (pin "1") (pinfunction "1_1") (pintype "passive"))
      (node (ref "C4_USB") (pin "1") (pinfunction "1_1") (pintype "passive"))
      (node (ref "C5_USB") (pin "1") (pinfunction "1_1") (pintype "passive"))
      (node (ref "CHG_LED") (pin "A") (pinfunction "A_A") (pintype "passive"))
      (node (ref "D1") (pin "5") (pinfunction "VBUS_5") (pintype "bidirectional"))
      (node (ref "D2") (pin "2") (pinfunction "ANODE_2") (pintype "bidirectional"))
      (node (ref "MCP73831") (pin "4") (pinfunction "VIN_4") (pintype "power_in"))
      (node (ref "PFMF.050.1") (pin "2") (pinfunction "2_2") (pintype "passive"))
      (node (ref "Q1") (pin "1") (pinfunction "G_1") (pintype "bidirectional"))
      (node (ref "R1_PWRUSB") (pin "2") (pinfunction "2_2") (pintype "passive"))
      (node (ref "TP14") (pin "TP") (pinfunction "TP_TP") (pintype "input"))
    )
    (net (code "54") (name "VRTC") (class "Default")
      (node (ref "C10_SUPERCAP") (pin "2") (pinfunction "2_2") (pintype "passive"))
      (node (ref "C8") (pin "1") (pinfunction "1_1") (pintype "passive"))
      (node (ref "R_CAPACITOR") (pin "1") (pinfunction "1_1") (pintype "passive"))
      (node (ref "U3") (pin "14") (pinfunction "VBAT_14") (pintype "power_in"))
    )
    (net (code "55") (name "VUSB") (class "Default")
      (node (ref "J2") (pin "A4") (pinfunction "A4_A4") (pintype "bidirectional"))
      (node (ref "J2") (pin "A9") (pinfunction "A9_A9") (pintype "bidirectional"))
      (node (ref "J2") (pin "B4") (pinfunction "B4_B4") (pintype "bidirectional"))
      (node (ref "J2") (pin "B9") (pinfunction "B9_B9") (pintype "bidirectional"))
      (node (ref "PFMF.050.1") (pin "1") (pinfunction "1_1") (pintype "passive"))
    )
    (net (code "56") (name "unconnected-(IC1-NC-Pad4)") (class "Default")
      (node (ref "IC1") (pin "4") (pinfunction "NC_4") (pintype "no_connect"))
    )
    (net (code "57") (name "unconnected-(IC4-NC-Pad4)") (class "Default")
      (node (ref "IC4") (pin "4") (pinfunction "NC_4") (pintype "no_connect"))
    )
    (net (code "58") (name "unconnected-(J1-Pad1)") (class "Default")
      (node (ref "J1") (pin "1") (pinfunction "1_1") (pintype "bidirectional"))
    )
    (net (code "59") (name "unconnected-(J1-Pad6)") (class "Default")
      (node (ref "J1") (pin "6") (pinfunction "6_6") (pintype "bidirectional"))
    )
    (net (code "60") (name "unconnected-(J1-Pad7)") (class "Default")
      (node (ref "J1") (pin "7") (pinfunction "7_7") (pintype "bidirectional"))
    )
    (net (code "61") (name "unconnected-(J2-PadA8)") (class "Default")
      (node (ref "J2") (pin "A8") (pinfunction "A8_A8") (pintype "bidirectional"))
    )
    (net (code "62") (name "unconnected-(J2-PadB8)") (class "Default")
      (node (ref "J2") (pin "B8") (pinfunction "B8_B8") (pintype "bidirectional"))
    )
    (net (code "63") (name "unconnected-(J4-DAT1-PadP8)") (class "Default")
      (node (ref "J4") (pin "P8") (pinfunction "DAT1_P8") (pintype "bidirectional"))
    )
    (net (code "64") (name "unconnected-(J4-DAT2-PadP1)") (class "Default")
      (node (ref "J4") (pin "P1") (pinfunction "DAT2_P1") (pintype "bidirectional"))
    )
    (net (code "65") (name "unconnected-(J4-DETECTION_1-PadS1)") (class "Default")
      (node (ref "J4") (pin "S1") (pinfunction "DETECTION_1_S1") (pintype "bidirectional"))
    )
    (net (code "66") (name "unconnected-(J4-DETECTION_2-PadS2)") (class "Default")
      (node (ref "J4") (pin "S2") (pinfunction "DETECTION_2_S2") (pintype "bidirectional"))
    )
    (net (code "67") (name "unconnected-(U2-NC-Pad22)") (class "Default")
      (node (ref "U2") (pin "22") (pinfunction "NC_22") (pintype "no_connect"))
    )
    (net (code "68") (name "unconnected-(U4-~{ALERT}-Pad5)") (class "Default")
      (node (ref "U4") (pin "5") (pinfunction "~{ALERT}_5") (pintype "output"))
    )
  )
)
